# TLV3501.net
KiCad netlist of a schematic drawn in Altium Designer
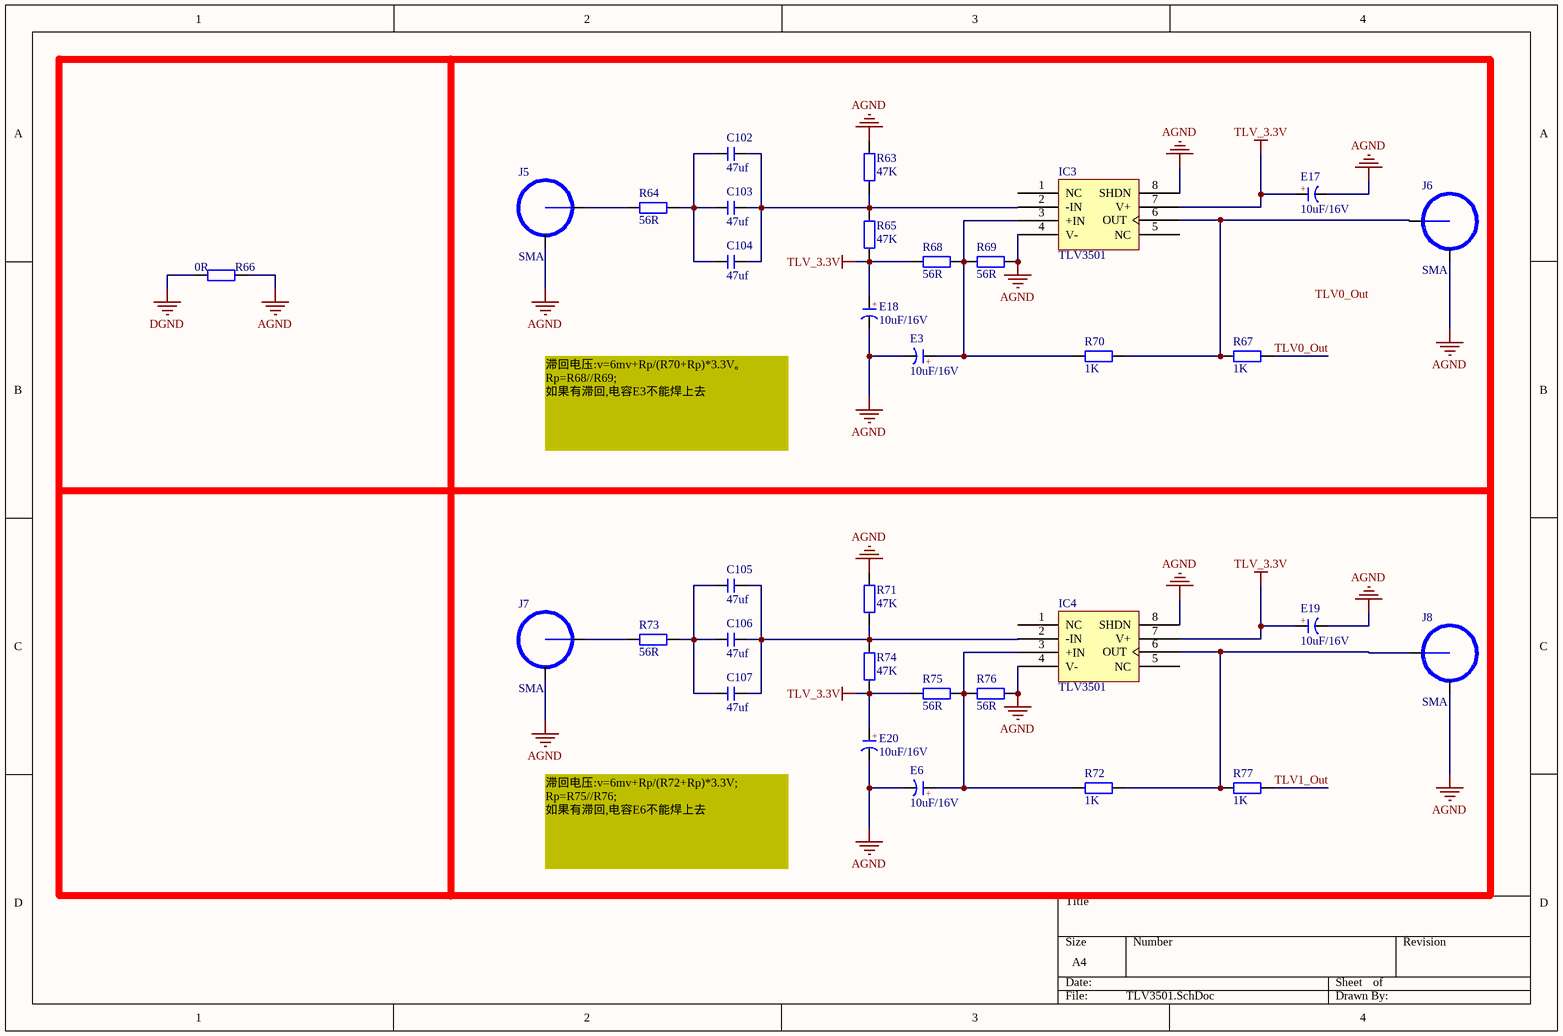
[diagram p0: TLV3501.SchDoc]

(export (version "E")
  (design (tool "Eeschema 10.0.6"))
  (components
    (comp (ref "C102")
      (value "47uf")
      (footprint "C 0805_M")
      (description "无极性贴片电容")
      (fields (field (name "版权归属") "源创客"))
      (libsource (lib "3.1   - 电阻-电容-电感") (part "C"))
    )
    (comp (ref "C103")
      (value "47uf")
      (footprint "C 0805_M")
      (description "无极性贴片电容")
      (fields (field (name "版权归属") "源创客"))
      (libsource (lib "3.1   - 电阻-电容-电感") (part "C"))
    )
    (comp (ref "C104")
      (value "47uf")
      (footprint "C 0805_M")
      (description "无极性贴片电容")
      (fields (field (name "版权归属") "源创客"))
      (libsource (lib "3.1   - 电阻-电容-电感") (part "C"))
    )
    (comp (ref "C105")
      (value "47uf")
      (footprint "C 0805_M")
      (description "无极性贴片电容")
      (fields (field (name "版权归属") "源创客"))
      (libsource (lib "3.1   - 电阻-电容-电感") (part "C"))
    )
    (comp (ref "C106")
      (value "47uf")
      (footprint "C 0805_M")
      (description "无极性贴片电容")
      (fields (field (name "版权归属") "源创客"))
      (libsource (lib "3.1   - 电阻-电容-电感") (part "C"))
    )
    (comp (ref "C107")
      (value "47uf")
      (footprint "C 0805_M")
      (description "无极性贴片电容")
      (fields (field (name "版权归属") "源创客"))
      (libsource (lib "3.1   - 电阻-电容-电感") (part "C"))
    )
    (comp (ref "E3")
      (value "10uF/16V")
      (footprint "C 1210_M")
      (description "直插电解电容")
      (fields (field (name "版权归属") "源创客"))
      (libsource (lib "3.1   - 电阻-电容-电感") (part "C-CAP"))
    )
    (comp (ref "E6")
      (value "10uF/16V")
      (footprint "C 1210_M")
      (description "直插电解电容")
      (fields (field (name "版权归属") "源创客"))
      (libsource (lib "3.1   - 电阻-电容-电感") (part "C-CAP"))
    )
    (comp (ref "E17")
      (value "10uF/16V")
      (footprint "C 1210_M")
      (description "直插电解电容")
      (fields (field (name "版权归属") "源创客"))
      (libsource (lib "3.1   - 电阻-电容-电感") (part "C-CAP"))
    )
    (comp (ref "E18")
      (value "10uF/16V")
      (footprint "C 1210_M")
      (description "直插电解电容")
      (fields (field (name "版权归属") "源创客"))
      (libsource (lib "") (part "C-CAP_1"))
    )
    (comp (ref "E19")
      (value "10uF/16V")
      (footprint "C 1210_M")
      (description "直插电解电容")
      (fields (field (name "版权归属") "源创客"))
      (libsource (lib "3.1   - 电阻-电容-电感") (part "C-CAP"))
    )
    (comp (ref "E20")
      (value "10uF/16V")
      (footprint "C 1210_M")
      (description "直插电解电容")
      (fields (field (name "版权归属") "源创客"))
      (libsource (lib "") (part "C-CAP_1"))
    )
    (comp (ref "IC3")
      (value "TLV3501")
      (footprint "SOP8_M")
      (description "外置EEPROM")
      (fields (field (name "版权归属") "源创客"))
      (libsource (lib "1.1   - IC芯片") (part "24Cxx"))
    )
    (comp (ref "IC4")
      (value "TLV3501")
      (footprint "SOP8_M")
      (description "外置EEPROM")
      (fields (field (name "版权归属") "源创客"))
      (libsource (lib "1.1   - IC芯片") (part "24Cxx"))
    )
    (comp (ref "J5") (value "SMA") (footprint "SMA_FR") (libsource (lib "") (part "SMA_1")))
    (comp (ref "J6") (value "SMA") (footprint "SMA_FR") (libsource (lib "电子竞赛") (part "SMA")))
    (comp (ref "J7") (value "SMA") (footprint "SMA_FR") (libsource (lib "") (part "SMA_1")))
    (comp (ref "J8") (value "SMA") (footprint "SMA_FR") (libsource (lib "电子竞赛") (part "SMA")))
    (comp (ref "R63")
      (value "47K")
      (footprint "R 0805_M")
      (description "贴片电阻")
      (fields (field (name "版权归属") "源创客"))
      (libsource (lib "3.1   - 电阻-电容-电感") (part "R"))
    )
    (comp (ref "R64")
      (value "56R")
      (footprint "R 0805_M")
      (description "贴片电阻")
      (fields (field (name "版权归属") "源创客"))
      (libsource (lib "3.1   - 电阻-电容-电感") (part "R"))
    )
    (comp (ref "R65")
      (value "47K")
      (footprint "R 0805_M")
      (description "贴片电阻")
      (fields (field (name "版权归属") "源创客"))
      (libsource (lib "3.1   - 电阻-电容-电感") (part "R"))
    )
    (comp (ref "R66")
      (value "0R")
      (footprint "R 0805_M")
      (description "贴片电阻")
      (fields (field (name "版权归属") "源创客"))
      (libsource (lib "3.1   - 电阻-电容-电感") (part "R"))
    )
    (comp (ref "R67")
      (value "1K")
      (footprint "R 0805_L")
      (description "贴片电阻")
      (fields (field (name "版权归属") "源创客"))
      (libsource (lib "3.1   - 电阻-电容-电感") (part "R"))
    )
    (comp (ref "R68")
      (value "56R")
      (footprint "R 0805_M")
      (description "贴片电阻")
      (fields (field (name "版权归属") "源创客"))
      (libsource (lib "3.1   - 电阻-电容-电感") (part "R"))
    )
    (comp (ref "R69")
      (value "56R")
      (footprint "R 0805_M")
      (description "贴片电阻")
      (fields (field (name "版权归属") "源创客"))
      (libsource (lib "3.1   - 电阻-电容-电感") (part "R"))
    )
    (comp (ref "R70")
      (value "1K")
      (footprint "R 0805_M")
      (description "贴片电阻")
      (fields (field (name "版权归属") "源创客"))
      (libsource (lib "3.1   - 电阻-电容-电感") (part "R"))
    )
    (comp (ref "R71")
      (value "47K")
      (footprint "R 0805_M")
      (description "贴片电阻")
      (fields (field (name "版权归属") "源创客"))
      (libsource (lib "3.1   - 电阻-电容-电感") (part "R"))
    )
    (comp (ref "R72")
      (value "1K")
      (footprint "R 0805_M")
      (description "贴片电阻")
      (fields (field (name "版权归属") "源创客"))
      (libsource (lib "3.1   - 电阻-电容-电感") (part "R"))
    )
    (comp (ref "R73")
      (value "56R")
      (footprint "R 0805_M")
      (description "贴片电阻")
      (fields (field (name "版权归属") "源创客"))
      (libsource (lib "3.1   - 电阻-电容-电感") (part "R"))
    )
    (comp (ref "R74")
      (value "47K")
      (footprint "R 0805_M")
      (description "贴片电阻")
      (fields (field (name "版权归属") "源创客"))
      (libsource (lib "3.1   - 电阻-电容-电感") (part "R"))
    )
    (comp (ref "R75")
      (value "56R")
      (footprint "R 0805_M")
      (description "贴片电阻")
      (fields (field (name "版权归属") "源创客"))
      (libsource (lib "3.1   - 电阻-电容-电感") (part "R"))
    )
    (comp (ref "R76")
      (value "56R")
      (footprint "R 0805_M")
      (description "贴片电阻")
      (fields (field (name "版权归属") "源创客"))
      (libsource (lib "3.1   - 电阻-电容-电感") (part "R"))
    )
    (comp (ref "R77")
      (value "1K")
      (footprint "R 0805_L")
      (description "贴片电阻")
      (fields (field (name "版权归属") "源创客"))
      (libsource (lib "3.1   - 电阻-电容-电感") (part "R"))
    )
  )
  (nets
    (net (code "1") (name "/TLV0_Out") (class "Default")
      (node (ref "R67") (pin "2") (pinfunction "2_2") (pintype "passive"))
    )
    (net (code "2") (name "/TLV1_Out") (class "Default")
      (node (ref "R77") (pin "2") (pinfunction "2_2") (pintype "passive"))
    )
    (net (code "3") (name "AGND") (class "Default")
      (node (ref "E17") (pin "2") (pinfunction "K_2") (pintype "passive"))
      (node (ref "E18") (pin "2") (pinfunction "K_2") (pintype "passive"))
      (node (ref "E19") (pin "2") (pinfunction "K_2") (pintype "passive"))
      (node (ref "E20") (pin "2") (pinfunction "K_2") (pintype "passive"))
      (node (ref "E3") (pin "2") (pinfunction "K_2") (pintype "passive"))
      (node (ref "E6") (pin "2") (pinfunction "K_2") (pintype "passive"))
      (node (ref "IC3") (pin "4") (pinfunction "V-_4") (pintype "passive"))
      (node (ref "IC3") (pin "8") (pinfunction "SHDN_8") (pintype "passive"))
      (node (ref "IC4") (pin "4") (pinfunction "V-_4") (pintype "passive"))
      (node (ref "IC4") (pin "8") (pinfunction "SHDN_8") (pintype "passive"))
      (node (ref "J5") (pin "2") (pinfunction "2_2") (pintype "passive"))
      (node (ref "J6") (pin "2") (pinfunction "2_2") (pintype "passive"))
      (node (ref "J7") (pin "2") (pinfunction "2_2") (pintype "passive"))
      (node (ref "J8") (pin "2") (pinfunction "2_2") (pintype "passive"))
      (node (ref "R63") (pin "2") (pinfunction "2_2") (pintype "passive"))
      (node (ref "R66") (pin "2") (pinfunction "2_2") (pintype "passive"))
      (node (ref "R69") (pin "1") (pinfunction "1_1") (pintype "passive"))
      (node (ref "R71") (pin "2") (pinfunction "2_2") (pintype "passive"))
      (node (ref "R76") (pin "1") (pinfunction "1_1") (pintype "passive"))
    )
    (net (code "4") (name "DGND") (class "Default")
      (node (ref "R66") (pin "1") (pinfunction "1_1") (pintype "passive"))
    )
    (net (code "5") (name "Net-(C102-Pad1)") (class "Default")
      (node (ref "C102") (pin "1") (pinfunction "1_1") (pintype "passive"))
      (node (ref "C103") (pin "1") (pinfunction "1_1") (pintype "passive"))
      (node (ref "C104") (pin "1") (pinfunction "1_1") (pintype "passive"))
      (node (ref "R64") (pin "1") (pinfunction "1_1") (pintype "passive"))
    )
    (net (code "6") (name "Net-(C105-Pad1)") (class "Default")
      (node (ref "C105") (pin "1") (pinfunction "1_1") (pintype "passive"))
      (node (ref "C106") (pin "1") (pinfunction "1_1") (pintype "passive"))
      (node (ref "C107") (pin "1") (pinfunction "1_1") (pintype "passive"))
      (node (ref "R73") (pin "1") (pinfunction "1_1") (pintype "passive"))
    )
    (net (code "7") (name "Net-(E3-A)") (class "Default")
      (node (ref "E3") (pin "1") (pinfunction "A_1") (pintype "passive"))
      (node (ref "IC3") (pin "3") (pinfunction "+IN_3") (pintype "passive"))
      (node (ref "R68") (pin "1") (pinfunction "1_1") (pintype "passive"))
      (node (ref "R69") (pin "2") (pinfunction "2_2") (pintype "passive"))
      (node (ref "R70") (pin "2") (pinfunction "2_2") (pintype "passive"))
    )
    (net (code "8") (name "Net-(E6-A)") (class "Default")
      (node (ref "E6") (pin "1") (pinfunction "A_1") (pintype "passive"))
      (node (ref "IC4") (pin "3") (pinfunction "+IN_3") (pintype "passive"))
      (node (ref "R72") (pin "2") (pinfunction "2_2") (pintype "passive"))
      (node (ref "R75") (pin "1") (pinfunction "1_1") (pintype "passive"))
      (node (ref "R76") (pin "2") (pinfunction "2_2") (pintype "passive"))
    )
    (net (code "9") (name "Net-(IC3--IN)") (class "Default")
      (node (ref "C102") (pin "2") (pinfunction "2_2") (pintype "passive"))
      (node (ref "C103") (pin "2") (pinfunction "2_2") (pintype "passive"))
      (node (ref "C104") (pin "2") (pinfunction "2_2") (pintype "passive"))
      (node (ref "IC3") (pin "2") (pinfunction "-IN_2") (pintype "passive"))
      (node (ref "R63") (pin "1") (pinfunction "1_1") (pintype "passive"))
      (node (ref "R65") (pin "2") (pinfunction "2_2") (pintype "passive"))
    )
    (net (code "10") (name "Net-(IC3-OUT)") (class "Default")
      (node (ref "IC3") (pin "6") (pinfunction "OUT_6") (pintype "passive"))
      (node (ref "J6") (pin "1") (pinfunction "1_1") (pintype "passive"))
      (node (ref "R67") (pin "1") (pinfunction "1_1") (pintype "passive"))
      (node (ref "R70") (pin "1") (pinfunction "1_1") (pintype "passive"))
    )
    (net (code "11") (name "Net-(IC4--IN)") (class "Default")
      (node (ref "C105") (pin "2") (pinfunction "2_2") (pintype "passive"))
      (node (ref "C106") (pin "2") (pinfunction "2_2") (pintype "passive"))
      (node (ref "C107") (pin "2") (pinfunction "2_2") (pintype "passive"))
      (node (ref "IC4") (pin "2") (pinfunction "-IN_2") (pintype "passive"))
      (node (ref "R71") (pin "1") (pinfunction "1_1") (pintype "passive"))
      (node (ref "R74") (pin "2") (pinfunction "2_2") (pintype "passive"))
    )
    (net (code "12") (name "Net-(IC4-OUT)") (class "Default")
      (node (ref "IC4") (pin "6") (pinfunction "OUT_6") (pintype "passive"))
      (node (ref "J8") (pin "1") (pinfunction "1_1") (pintype "passive"))
      (node (ref "R72") (pin "1") (pinfunction "1_1") (pintype "passive"))
      (node (ref "R77") (pin "1") (pinfunction "1_1") (pintype "passive"))
    )
    (net (code "13") (name "Net-(J5-Pad1)") (class "Default")
      (node (ref "J5") (pin "1") (pinfunction "1_1") (pintype "passive"))
      (node (ref "R64") (pin "2") (pinfunction "2_2") (pintype "passive"))
    )
    (net (code "14") (name "Net-(J7-Pad1)") (class "Default")
      (node (ref "J7") (pin "1") (pinfunction "1_1") (pintype "passive"))
      (node (ref "R73") (pin "2") (pinfunction "2_2") (pintype "passive"))
    )
    (net (code "15") (name "TLV_3.3V") (class "Default")
      (node (ref "E17") (pin "1") (pinfunction "A_1") (pintype "passive"))
      (node (ref "E18") (pin "1") (pinfunction "A_1") (pintype "passive"))
      (node (ref "E19") (pin "1") (pinfunction "A_1") (pintype "passive"))
      (node (ref "E20") (pin "1") (pinfunction "A_1") (pintype "passive"))
      (node (ref "IC3") (pin "7") (pinfunction "V+_7") (pintype "passive"))
      (node (ref "IC4") (pin "7") (pinfunction "V+_7") (pintype "passive"))
      (node (ref "R65") (pin "1") (pinfunction "1_1") (pintype "passive"))
      (node (ref "R68") (pin "2") (pinfunction "2_2") (pintype "passive"))
      (node (ref "R74") (pin "1") (pinfunction "1_1") (pintype "passive"))
      (node (ref "R75") (pin "2") (pinfunction "2_2") (pintype "passive"))
    )
    (net (code "16") (name "unconnected-(IC3-NC-Pad1)") (class "Default")
      (node (ref "IC3") (pin "1") (pinfunction "NC_1") (pintype "passive"))
    )
    (net (code "17") (name "unconnected-(IC3-NC-Pad5)") (class "Default")
      (node (ref "IC3") (pin "5") (pinfunction "NC_5") (pintype "passive"))
    )
    (net (code "18") (name "unconnected-(IC4-NC-Pad1)") (class "Default")
      (node (ref "IC4") (pin "1") (pinfunction "NC_1") (pintype "passive"))
    )
    (net (code "19") (name "unconnected-(IC4-NC-Pad5)") (class "Default")
      (node (ref "IC4") (pin "5") (pinfunction "NC_5") (pintype "passive"))
    )
  )
)
